# AST1041.net
KiCad netlist of a schematic drawn in EAGLE
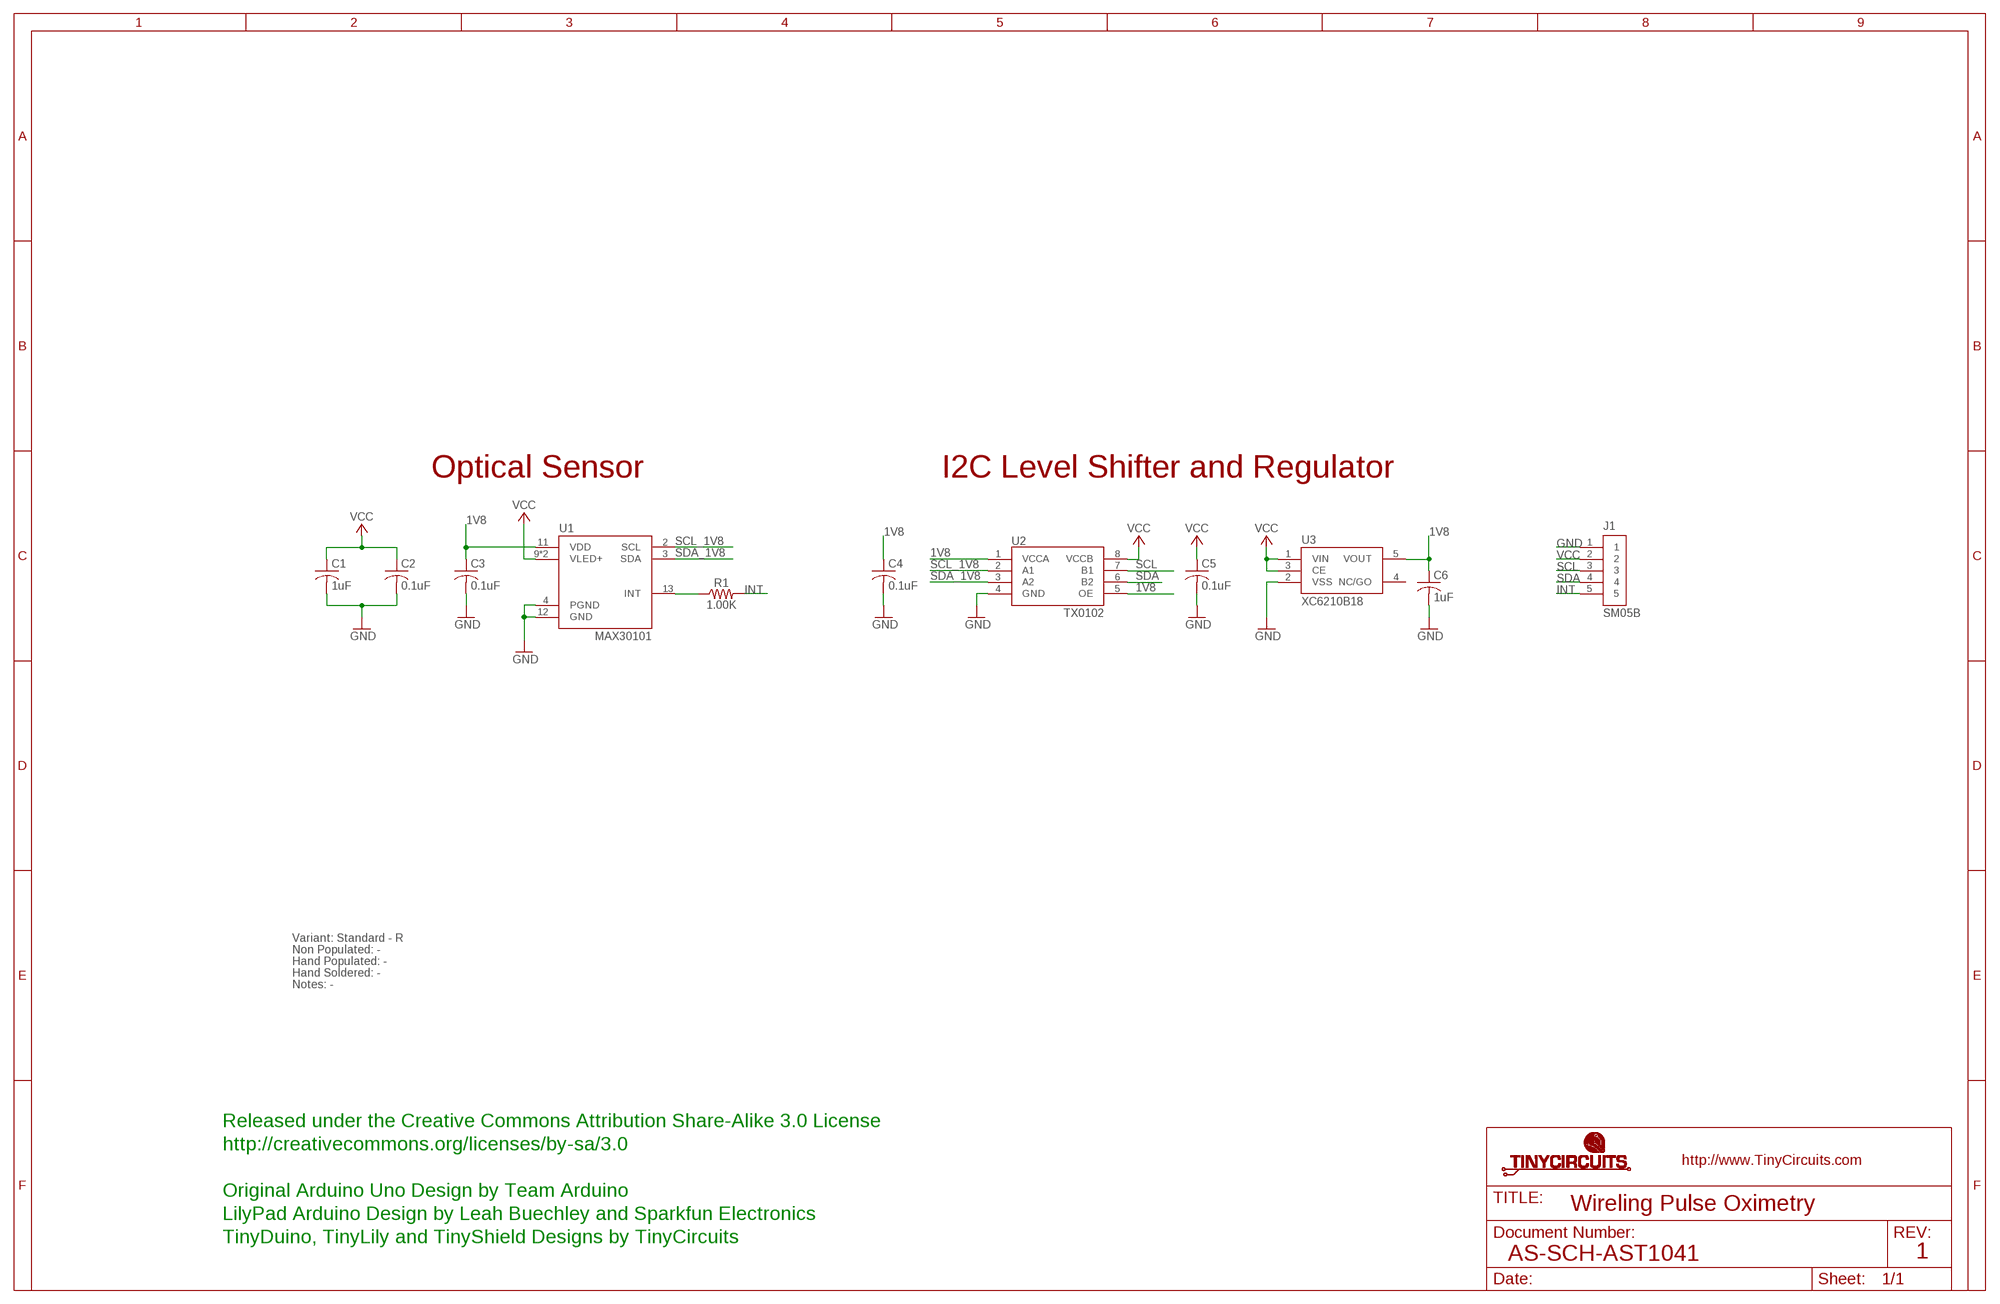
[diagram p0: schematic, sheet 1]

(export (version "E")
  (design (tool "Eeschema 10.0.6"))
  (components
    (comp (ref "C1")
      (value "1uF")
      (footprint "eagle-import:C0402")
      (fields (field (name "PARTNO") "AS-ITM-00105") (field (name "PARTNO_1") "AS-ITM-00105"))
      (libsource (lib "eagle-import") (part "AS-ITM-00105"))
    )
    (comp (ref "C2")
      (value "0.1uF")
      (footprint "eagle-import:C0402")
      (fields (field (name "PARTNO") "AS-ITM-00008"))
      (libsource (lib "eagle-import") (part "AS-ITM-00008"))
    )
    (comp (ref "C3")
      (value "0.1uF")
      (footprint "eagle-import:C0402")
      (fields (field (name "PARTNO") "AS-ITM-00008") (field (name "PARTNO_1") "AS-ITM-00008"))
      (libsource (lib "eagle-import") (part "AS-ITM-00008"))
    )
    (comp (ref "C4")
      (value "0.1uF")
      (footprint "eagle-import:C0402")
      (fields (field (name "PARTNO") "AS-ITM-00008") (field (name "PARTNO_1") "AS-ITM-00008"))
      (libsource (lib "eagle-import") (part "AS-ITM-00008"))
    )
    (comp (ref "C5")
      (value "0.1uF")
      (footprint "eagle-import:C0402")
      (fields (field (name "PARTNO") "AS-ITM-00008") (field (name "PARTNO_1") "AS-ITM-00008"))
      (libsource (lib "eagle-import") (part "AS-ITM-00008"))
    )
    (comp (ref "C6")
      (value "1uF")
      (footprint "eagle-import:C0402")
      (fields (field (name "PARTNO") "AS-ITM-00105") (field (name "PARTNO_1") "AS-ITM-00105"))
      (libsource (lib "eagle-import") (part "AS-ITM-00105"))
    )
    (comp (ref "J1")
      (value "SM05B")
      (footprint "eagle-import:JST_SH_5X1_EDGE")
      (fields (field (name "PARTNO") "AS-ITM-00340"))
      (libsource (lib "eagle-import") (part "AS-ITM-00340EDGE"))
    )
    (comp (ref "R1")
      (value "1.00K")
      (footprint "eagle-import:0402")
      (fields (field (name "PARTNO") "AS-ITM-00003"))
      (libsource (lib "eagle-import") (part "AS-ITM-00003"))
    )
    (comp (ref "U1")
      (value "MAX30101")
      (footprint "eagle-import:MAX30100")
      (fields (field (name "PARTNO") "AS-ITM-00473"))
      (libsource (lib "eagle-import") (part "AS-ITM-00473"))
    )
    (comp (ref "U2")
      (value "TX0102")
      (footprint "eagle-import:DQE(R-PX2SON-N8)")
      (fields (field (name "PARTNO") "AS-ITM-00073"))
      (libsource (lib "eagle-import") (part "AS-ITM-00073"))
    )
    (comp (ref "U3")
      (value "XC6210B18")
      (footprint "eagle-import:SOT-25")
      (fields (field (name "PARTNO") "AS-ITM-00075"))
      (libsource (lib "eagle-import") (part "AS-ITM-00075"))
    )
  )
  (nets
    (net (code "1") (name "/1V8") (class "Default")
      (node (ref "C3") (pin "1") (pinfunction "1_1") (pintype "passive"))
      (node (ref "C4") (pin "1") (pinfunction "1_1") (pintype "passive"))
      (node (ref "C6") (pin "1") (pinfunction "1_1") (pintype "passive"))
      (node (ref "U1") (pin "11") (pinfunction "VDD_11") (pintype "bidirectional"))
      (node (ref "U2") (pin "1") (pinfunction "VCCA_1") (pintype "bidirectional"))
      (node (ref "U2") (pin "5") (pinfunction "OE_5") (pintype "bidirectional"))
      (node (ref "U3") (pin "5") (pinfunction "VOUT_5") (pintype "bidirectional"))
    )
    (net (code "2") (name "/INT") (class "Default")
      (node (ref "J1") (pin "5") (pinfunction "5_5") (pintype "bidirectional"))
      (node (ref "R1") (pin "2") (pinfunction "2_2") (pintype "passive"))
    )
    (net (code "3") (name "/SCL") (class "Default")
      (node (ref "J1") (pin "3") (pinfunction "3_3") (pintype "bidirectional"))
      (node (ref "U2") (pin "7") (pinfunction "B1_7") (pintype "bidirectional"))
    )
    (net (code "4") (name "/SCL_1V8") (class "Default")
      (node (ref "U1") (pin "2") (pinfunction "SCL_2") (pintype "bidirectional"))
      (node (ref "U2") (pin "2") (pinfunction "A1_2") (pintype "bidirectional"))
    )
    (net (code "5") (name "/SDA") (class "Default")
      (node (ref "J1") (pin "4") (pinfunction "4_4") (pintype "bidirectional"))
      (node (ref "U2") (pin "6") (pinfunction "B2_6") (pintype "bidirectional"))
    )
    (net (code "6") (name "/SDA_1V8") (class "Default")
      (node (ref "U1") (pin "3") (pinfunction "SDA_3") (pintype "bidirectional"))
      (node (ref "U2") (pin "3") (pinfunction "A2_3") (pintype "bidirectional"))
    )
    (net (code "7") (name "GND") (class "Default")
      (node (ref "C1") (pin "2") (pinfunction "2_2") (pintype "passive"))
      (node (ref "C2") (pin "2") (pinfunction "2_2") (pintype "passive"))
      (node (ref "C3") (pin "2") (pinfunction "2_2") (pintype "passive"))
      (node (ref "C4") (pin "2") (pinfunction "2_2") (pintype "passive"))
      (node (ref "C5") (pin "2") (pinfunction "2_2") (pintype "passive"))
      (node (ref "C6") (pin "2") (pinfunction "2_2") (pintype "passive"))
      (node (ref "J1") (pin "1") (pinfunction "1_1") (pintype "bidirectional"))
      (node (ref "U1") (pin "12") (pinfunction "GND_12") (pintype "bidirectional"))
      (node (ref "U1") (pin "4") (pinfunction "PGND_4") (pintype "bidirectional"))
      (node (ref "U2") (pin "4") (pinfunction "GND_4") (pintype "bidirectional"))
      (node (ref "U3") (pin "2") (pinfunction "VSS_2") (pintype "power_in"))
    )
    (net (code "8") (name "Net-(U1-INT)") (class "Default")
      (node (ref "R1") (pin "1") (pinfunction "1_1") (pintype "passive"))
      (node (ref "U1") (pin "13") (pinfunction "INT_13") (pintype "bidirectional"))
    )
    (net (code "9") (name "VCC") (class "Default")
      (node (ref "C1") (pin "1") (pinfunction "1_1") (pintype "passive"))
      (node (ref "C2") (pin "1") (pinfunction "1_1") (pintype "passive"))
      (node (ref "C5") (pin "1") (pinfunction "1_1") (pintype "passive"))
      (node (ref "J1") (pin "2") (pinfunction "2_2") (pintype "bidirectional"))
      (node (ref "U1") (pin "10") (pinfunction "VLED+_10") (pintype "bidirectional"))
      (node (ref "U1") (pin "9") (pinfunction "VLED+_9") (pintype "bidirectional"))
      (node (ref "U2") (pin "8") (pinfunction "VCCB_8") (pintype "bidirectional"))
      (node (ref "U3") (pin "1") (pinfunction "VIN_1") (pintype "bidirectional"))
      (node (ref "U3") (pin "3") (pinfunction "CE_3") (pintype "bidirectional"))
    )
    (net (code "10") (name "unconnected-(U3-NC{slash}GO-Pad4)") (class "Default")
      (node (ref "U3") (pin "4") (pinfunction "NC/GO_4") (pintype "bidirectional"))
    )
  )
)
